# 1_mcuv4.net
KiCad netlist of a schematic drawn in Altium Designer
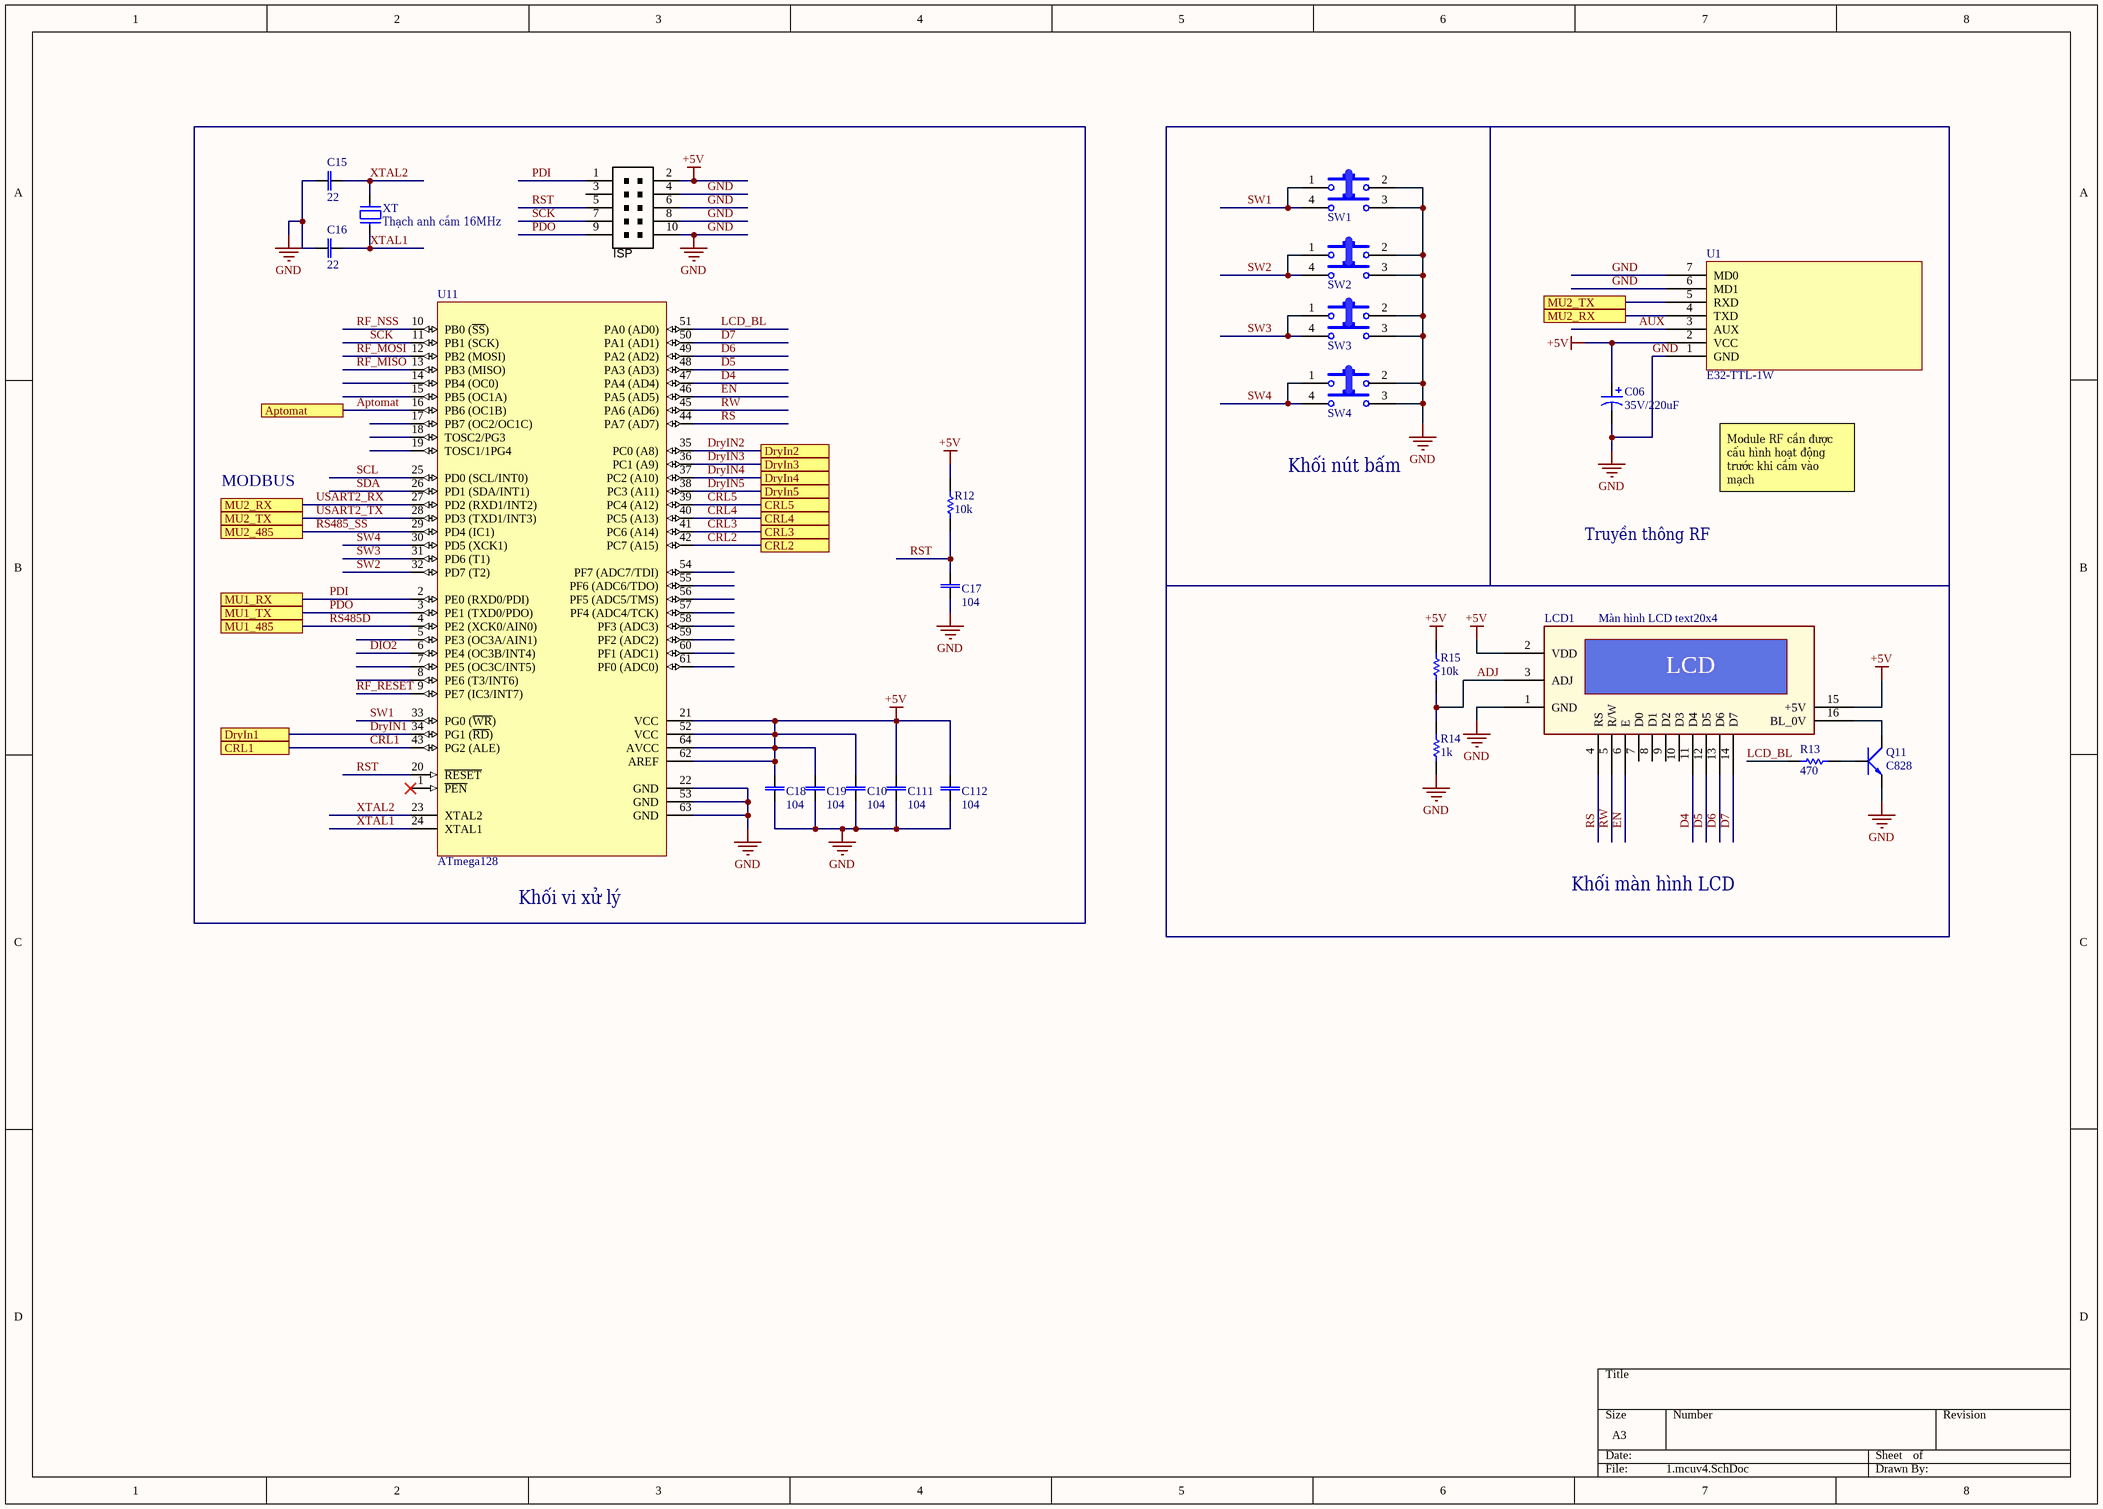
[diagram p0: 1.mcuv4.SchDoc]

(export (version "E")
  (design (tool "Eeschema 10.0.6"))
  (components
    (comp (ref "C06")
      (value "35V/220uF")
      (footprint "CAPE3.5-5.0MM_Rad_10x14mm")
      (fields (field (name "Comment") "Tụ nhôm cắm35V/220uF"))
      (libsource (lib "Tuan") (part "Cap"))
    )
    (comp (ref "C10")
      (value "104")
      (footprint "swatpcblib:CAP 0805")
      (description "Capacitor non polarized")
      (fields (field (name "Comment") "Tụ điện dán 0805104"))
      (libsource (lib "swatpcblib") (part "CAP NP"))
    )
    (comp (ref "C15")
      (value "22")
      (footprint "swatpcblib:CAP 0805")
      (description "Capacitor non polarized")
      (fields (field (name "Comment") "Tụ điện dán 080522"))
      (libsource (lib "swatpcblib") (part "CAP NP"))
    )
    (comp (ref "C16")
      (value "22")
      (footprint "swatpcblib:CAP 0805")
      (description "Capacitor non polarized")
      (fields (field (name "Comment") "Tụ điện dán 080522"))
      (libsource (lib "swatpcblib") (part "CAP NP"))
    )
    (comp (ref "C17")
      (value "104")
      (footprint "swatpcblib:CAP 0805")
      (description "Capacitor non polarized")
      (fields (field (name "Comment") "Tụ điện dán 0805104"))
      (libsource (lib "swatpcblib") (part "CAP NP"))
    )
    (comp (ref "C18")
      (value "104")
      (footprint "swatpcblib:CAP 0805")
      (description "Capacitor non polarized")
      (fields (field (name "Comment") "Tụ điện dán 0805104"))
      (libsource (lib "swatpcblib") (part "CAP NP"))
    )
    (comp (ref "C19")
      (value "104")
      (footprint "swatpcblib:CAP 0805")
      (description "Capacitor non polarized")
      (fields (field (name "Comment") "Tụ điện dán 0805104"))
      (libsource (lib "swatpcblib") (part "CAP NP"))
    )
    (comp (ref "C111")
      (value "104")
      (footprint "swatpcblib:CAP 0805")
      (description "Capacitor non polarized")
      (fields (field (name "Comment") "Tụ điện dán 0805104"))
      (libsource (lib "swatpcblib") (part "CAP NP"))
    )
    (comp (ref "C112")
      (value "104")
      (footprint "swatpcblib:CAP 0805")
      (description "Capacitor non polarized")
      (fields (field (name "Comment") "Tụ điện dán 0805104"))
      (libsource (lib "swatpcblib") (part "CAP NP"))
    )
    (comp (ref "ISP")
      (value "Giắc đôi 5x2 chân 2.54mm")
      (footprint "10P_PCB_HEADER_BRD_MNT")
      (description "Header THD 10 POS Double-row 2.54mm pitch")
      (libsource (lib "PBL - Connectors") (part "CONN_HEADER_2x5P_0.100in_Male"))
    )
    (comp (ref "LCD1")
      (value "Màn hình LCD text20x4")
      (footprint "LCD 20x4")
      (description "Text LCD")
      (libsource (lib "Tuan") (part "LCD 16x2"))
    )
    (comp (ref "Q11")
      (value "C828")
      (footprint "SOT23 TOP")
      (description "Transistor C828 C1815....")
      (libsource (lib "Tuan") (part "NPN"))
    )
    (comp (ref "R12")
      (value "10k")
      (footprint "swatpcblib:RES 0805")
      (description "Resistor")
      (fields (field (name "Comment") "Điện trở dán 080510k"))
      (libsource (lib "swatpcblib") (part "Res"))
    )
    (comp (ref "R13")
      (value "470")
      (footprint "PBL - SMD Packages:RESC1608N_F")
      (description "Resistor")
      (fields (field (name "Comment") "Điện trở dán 0805470"))
      (libsource (lib "swatpcblib") (part "Res"))
    )
    (comp (ref "R14")
      (value "1k")
      (footprint "swatpcblib:RES 0805")
      (description "Resistor")
      (fields (field (name "Comment") "Điện trở dán 08051k"))
      (libsource (lib "swatpcblib") (part "Res"))
    )
    (comp (ref "R15")
      (value "10k")
      (footprint "swatpcblib:RES 0805")
      (description "Resistor")
      (fields (field (name "Comment") "Điện trở dán 080510k"))
      (libsource (lib "swatpcblib") (part "Res"))
    )
    (comp (ref "SW1")
      (value "Nút bấm 4 chân cắm12x12x17mm")
      (footprint "hayqua:SW 12x12x4")
      (libsource (lib "Tuan") (part "SW-4P-Small"))
    )
    (comp (ref "SW2")
      (value "Nút bấm 4 chân cắm12x12x17mm")
      (footprint "hayqua:SW 12x12x4")
      (libsource (lib "Tuan") (part "SW-4P-Small"))
    )
    (comp (ref "SW3")
      (value "Nút bấm 4 chân cắm12x12x17mm")
      (footprint "hayqua:SW 12x12x4")
      (libsource (lib "Tuan") (part "SW-4P-Small"))
    )
    (comp (ref "SW4")
      (value "Nút bấm 4 chân cắm12x12x17mm")
      (footprint "hayqua:SW 12x12x4")
      (libsource (lib "Tuan") (part "SW-4P-Small"))
    )
    (comp (ref "U1")
      (value "E32-TTL-1W")
      (footprint "RF_AS32")
      (description "AS32-TTL-1W")
      (fields (field (name "Comment") "Module thu phát không dây RFE32-TTL-1W"))
      (libsource (lib "DnsSchLib") (part "AS32-TTL-1W"))
    )
    (comp (ref "U11")
      (value "ATmega128")
      (footprint "64A_N")
      (description "8-Bit AVR Microcontroller with 128K Bytes of In-System Programmable Flash Memory")
      (fields (field (name "PUBLISHER") "Altium Limited"))
      (libsource (lib "Atmel Microcontroller 8-Bit AVR") (part "ATmega128-16AC"))
    )
    (comp (ref "XT")
      (value "Thạch anh cắm 16MHz")
      (footprint "XT2")
      (libsource (lib "Tuan") (part "Crystal"))
    )
  )
  (nets
    (net (code "1") (name "+5V") (class "Default")
      (node (ref "C06") (pin "1") (pinfunction "1_1") (pintype "passive"))
      (node (ref "C10") (pin "2") (pinfunction "2_2") (pintype "passive"))
      (node (ref "C111") (pin "2") (pinfunction "2_2") (pintype "passive"))
      (node (ref "C112") (pin "2") (pinfunction "2_2") (pintype "passive"))
      (node (ref "C18") (pin "2") (pinfunction "2_2") (pintype "passive"))
      (node (ref "C19") (pin "2") (pinfunction "2_2") (pintype "passive"))
      (node (ref "ISP") (pin "2") (pinfunction "2_2") (pintype "passive"))
      (node (ref "LCD1") (pin "15") (pinfunction "+5V_15") (pintype "passive"))
      (node (ref "LCD1") (pin "2") (pinfunction "VDD_2") (pintype "passive"))
      (node (ref "R12") (pin "2") (pinfunction "2_2") (pintype "passive"))
      (node (ref "R15") (pin "2") (pinfunction "2_2") (pintype "passive"))
      (node (ref "U1") (pin "2") (pinfunction "VCC_2") (pintype "passive"))
      (node (ref "U11") (pin "21") (pinfunction "VCC_21") (pintype "power_in"))
      (node (ref "U11") (pin "52") (pinfunction "VCC_52") (pintype "power_in"))
      (node (ref "U11") (pin "62") (pinfunction "AREF_62") (pintype "passive"))
      (node (ref "U11") (pin "64") (pinfunction "AVCC_64") (pintype "power_in"))
    )
    (net (code "2") (name "/ADJ") (class "Default")
      (node (ref "LCD1") (pin "3") (pinfunction "ADJ_3") (pintype "passive"))
      (node (ref "R14") (pin "2") (pinfunction "2_2") (pintype "passive"))
      (node (ref "R15") (pin "1") (pinfunction "1_1") (pintype "passive"))
    )
    (net (code "3") (name "/AUX") (class "Default")
      (node (ref "U1") (pin "3") (pinfunction "AUX_3") (pintype "passive"))
    )
    (net (code "4") (name "/Aptomat") (class "Default")
      (node (ref "U11") (pin "16") (pinfunction "PB6_(OC1B)_16") (pintype "bidirectional"))
    )
    (net (code "5") (name "/CRL1") (class "Default")
      (node (ref "U11") (pin "43") (pinfunction "PG2_(ALE)_43") (pintype "bidirectional"))
    )
    (net (code "6") (name "/CRL2") (class "Default")
      (node (ref "U11") (pin "42") (pinfunction "PC7_(A15)_42") (pintype "bidirectional"))
    )
    (net (code "7") (name "/CRL3") (class "Default")
      (node (ref "U11") (pin "41") (pinfunction "PC6_(A14)_41") (pintype "bidirectional"))
    )
    (net (code "8") (name "/CRL4") (class "Default")
      (node (ref "U11") (pin "40") (pinfunction "PC5_(A13)_40") (pintype "bidirectional"))
    )
    (net (code "9") (name "/CRL5") (class "Default")
      (node (ref "U11") (pin "39") (pinfunction "PC4_(A12)_39") (pintype "bidirectional"))
    )
    (net (code "10") (name "/D4") (class "Default")
      (node (ref "LCD1") (pin "11") (pinfunction "D4_11") (pintype "passive"))
      (node (ref "U11") (pin "47") (pinfunction "PA4_(AD4)_47") (pintype "bidirectional"))
    )
    (net (code "11") (name "/D5") (class "Default")
      (node (ref "LCD1") (pin "12") (pinfunction "D5_12") (pintype "passive"))
      (node (ref "U11") (pin "48") (pinfunction "PA3_(AD3)_48") (pintype "bidirectional"))
    )
    (net (code "12") (name "/D6") (class "Default")
      (node (ref "LCD1") (pin "13") (pinfunction "D6_13") (pintype "passive"))
      (node (ref "U11") (pin "49") (pinfunction "PA2_(AD2)_49") (pintype "bidirectional"))
    )
    (net (code "13") (name "/D7") (class "Default")
      (node (ref "LCD1") (pin "14") (pinfunction "D7_14") (pintype "passive"))
      (node (ref "U11") (pin "50") (pinfunction "PA1_(AD1)_50") (pintype "bidirectional"))
    )
    (net (code "14") (name "/DIO2") (class "Default")
      (node (ref "U11") (pin "6") (pinfunction "PE4_(OC3B/INT4)_6") (pintype "bidirectional"))
    )
    (net (code "15") (name "/DryIN1") (class "Default")
      (node (ref "U11") (pin "34") (pinfunction "PG1_(~{RD})_34") (pintype "bidirectional"))
    )
    (net (code "16") (name "/DryIN2") (class "Default")
      (node (ref "U11") (pin "35") (pinfunction "PC0_(A8)_35") (pintype "bidirectional"))
    )
    (net (code "17") (name "/DryIN3") (class "Default")
      (node (ref "U11") (pin "36") (pinfunction "PC1_(A9)_36") (pintype "bidirectional"))
    )
    (net (code "18") (name "/DryIN4") (class "Default")
      (node (ref "U11") (pin "37") (pinfunction "PC2_(A10)_37") (pintype "bidirectional"))
    )
    (net (code "19") (name "/DryIN5") (class "Default")
      (node (ref "U11") (pin "38") (pinfunction "PC3_(A11)_38") (pintype "bidirectional"))
    )
    (net (code "20") (name "/EN") (class "Default")
      (node (ref "LCD1") (pin "6") (pinfunction "E_6") (pintype "passive"))
      (node (ref "U11") (pin "46") (pinfunction "PA5_(AD5)_46") (pintype "bidirectional"))
    )
    (net (code "21") (name "/LCD_BL") (class "Default")
      (node (ref "R13") (pin "2") (pinfunction "2_2") (pintype "passive"))
      (node (ref "U11") (pin "51") (pinfunction "PA0_(AD0)_51") (pintype "bidirectional"))
    )
    (net (code "22") (name "/PDI") (class "Default")
      (node (ref "ISP") (pin "1") (pinfunction "1_1") (pintype "passive"))
      (node (ref "U11") (pin "2") (pinfunction "PE0_(RXD0/PDI)_2") (pintype "bidirectional"))
    )
    (net (code "23") (name "/PDO") (class "Default")
      (node (ref "ISP") (pin "9") (pinfunction "9_9") (pintype "passive"))
      (node (ref "U11") (pin "3") (pinfunction "PE1_(TXD0/PDO)_3") (pintype "bidirectional"))
    )
    (net (code "24") (name "/RF_MISO") (class "Default")
      (node (ref "U11") (pin "13") (pinfunction "PB3_(MISO)_13") (pintype "bidirectional"))
    )
    (net (code "25") (name "/RF_MOSI") (class "Default")
      (node (ref "U11") (pin "12") (pinfunction "PB2_(MOSI)_12") (pintype "bidirectional"))
    )
    (net (code "26") (name "/RF_NSS") (class "Default")
      (node (ref "U11") (pin "10") (pinfunction "PB0_(~{SS})_10") (pintype "bidirectional"))
    )
    (net (code "27") (name "/RF_RESET") (class "Default")
      (node (ref "U11") (pin "9") (pinfunction "PE7_(IC3/INT7)_9") (pintype "bidirectional"))
    )
    (net (code "28") (name "/RS") (class "Default")
      (node (ref "LCD1") (pin "4") (pinfunction "RS_4") (pintype "passive"))
      (node (ref "U11") (pin "44") (pinfunction "PA7_(AD7)_44") (pintype "bidirectional"))
    )
    (net (code "29") (name "/RS485D") (class "Default")
      (node (ref "U11") (pin "4") (pinfunction "PE2_(XCK0/AIN0)_4") (pintype "bidirectional"))
    )
    (net (code "30") (name "/RS485_SS") (class "Default")
      (node (ref "U11") (pin "29") (pinfunction "PD4_(IC1)_29") (pintype "bidirectional"))
    )
    (net (code "31") (name "/RST") (class "Default")
      (node (ref "C17") (pin "2") (pinfunction "2_2") (pintype "passive"))
      (node (ref "ISP") (pin "5") (pinfunction "5_5") (pintype "passive"))
      (node (ref "R12") (pin "1") (pinfunction "1_1") (pintype "passive"))
      (node (ref "U11") (pin "20") (pinfunction "~{RESET}_20") (pintype "input"))
    )
    (net (code "32") (name "/RW") (class "Default")
      (node (ref "LCD1") (pin "5") (pinfunction "R/W_5") (pintype "passive"))
      (node (ref "U11") (pin "45") (pinfunction "PA6_(AD6)_45") (pintype "bidirectional"))
    )
    (net (code "33") (name "/SCK") (class "Default")
      (node (ref "ISP") (pin "7") (pinfunction "7_7") (pintype "passive"))
      (node (ref "U11") (pin "11") (pinfunction "PB1_(SCK)_11") (pintype "bidirectional"))
    )
    (net (code "34") (name "/SCL") (class "Default")
      (node (ref "U11") (pin "25") (pinfunction "PD0_(SCL/INT0)_25") (pintype "bidirectional"))
    )
    (net (code "35") (name "/SDA") (class "Default")
      (node (ref "U11") (pin "26") (pinfunction "PD1_(SDA/INT1)_26") (pintype "bidirectional"))
    )
    (net (code "36") (name "/SW1") (class "Default")
      (node (ref "SW1") (pin "1") (pinfunction "1_1") (pintype "passive"))
      (node (ref "SW1") (pin "4") (pinfunction "4_4") (pintype "passive"))
      (node (ref "U11") (pin "33") (pinfunction "PG0_(~{WR})_33") (pintype "bidirectional"))
    )
    (net (code "37") (name "/SW2") (class "Default")
      (node (ref "SW2") (pin "1") (pinfunction "1_1") (pintype "passive"))
      (node (ref "SW2") (pin "4") (pinfunction "4_4") (pintype "passive"))
      (node (ref "U11") (pin "32") (pinfunction "PD7_(T2)_32") (pintype "bidirectional"))
    )
    (net (code "38") (name "/SW3") (class "Default")
      (node (ref "SW3") (pin "1") (pinfunction "1_1") (pintype "passive"))
      (node (ref "SW3") (pin "4") (pinfunction "4_4") (pintype "passive"))
      (node (ref "U11") (pin "31") (pinfunction "PD6_(T1)_31") (pintype "bidirectional"))
    )
    (net (code "39") (name "/SW4") (class "Default")
      (node (ref "SW4") (pin "1") (pinfunction "1_1") (pintype "passive"))
      (node (ref "SW4") (pin "4") (pinfunction "4_4") (pintype "passive"))
      (node (ref "U11") (pin "30") (pinfunction "PD5_(XCK1)_30") (pintype "bidirectional"))
    )
    (net (code "40") (name "/USART2_RX") (class "Default")
      (node (ref "U1") (pin "4") (pinfunction "TXD_4") (pintype "passive"))
      (node (ref "U11") (pin "27") (pinfunction "PD2_(RXD1/INT2)_27") (pintype "bidirectional"))
    )
    (net (code "41") (name "/USART2_TX") (class "Default")
      (node (ref "U1") (pin "5") (pinfunction "RXD_5") (pintype "passive"))
      (node (ref "U11") (pin "28") (pinfunction "PD3_(TXD1/INT3)_28") (pintype "bidirectional"))
    )
    (net (code "42") (name "/XTAL1") (class "Default")
      (node (ref "C16") (pin "1") (pinfunction "1_1") (pintype "passive"))
      (node (ref "U11") (pin "24") (pinfunction "XTAL1_24") (pintype "passive"))
      (node (ref "XT") (pin "1") (pinfunction "1_1") (pintype "passive"))
    )
    (net (code "43") (name "/XTAL2") (class "Default")
      (node (ref "C15") (pin "1") (pinfunction "1_1") (pintype "passive"))
      (node (ref "U11") (pin "23") (pinfunction "XTAL2_23") (pintype "passive"))
      (node (ref "XT") (pin "2") (pinfunction "2_2") (pintype "passive"))
    )
    (net (code "44") (name "GND") (class "Default")
      (node (ref "C06") (pin "2") (pinfunction "2_2") (pintype "passive"))
      (node (ref "C10") (pin "1") (pinfunction "1_1") (pintype "passive"))
      (node (ref "C111") (pin "1") (pinfunction "1_1") (pintype "passive"))
      (node (ref "C112") (pin "1") (pinfunction "1_1") (pintype "passive"))
      (node (ref "C15") (pin "2") (pinfunction "2_2") (pintype "passive"))
      (node (ref "C16") (pin "2") (pinfunction "2_2") (pintype "passive"))
      (node (ref "C17") (pin "1") (pinfunction "1_1") (pintype "passive"))
      (node (ref "C18") (pin "1") (pinfunction "1_1") (pintype "passive"))
      (node (ref "C19") (pin "1") (pinfunction "1_1") (pintype "passive"))
      (node (ref "ISP") (pin "10") (pinfunction "10_10") (pintype "passive"))
      (node (ref "ISP") (pin "4") (pinfunction "4_4") (pintype "passive"))
      (node (ref "ISP") (pin "6") (pinfunction "6_6") (pintype "passive"))
      (node (ref "ISP") (pin "8") (pinfunction "8_8") (pintype "passive"))
      (node (ref "LCD1") (pin "1") (pinfunction "GND_1") (pintype "passive"))
      (node (ref "Q11") (pin "3") (pinfunction "E_3") (pintype "passive"))
      (node (ref "R14") (pin "1") (pinfunction "1_1") (pintype "passive"))
      (node (ref "SW1") (pin "2") (pinfunction "2_2") (pintype "passive"))
      (node (ref "SW1") (pin "3") (pinfunction "3_3") (pintype "passive"))
      (node (ref "SW2") (pin "2") (pinfunction "2_2") (pintype "passive"))
      (node (ref "SW2") (pin "3") (pinfunction "3_3") (pintype "passive"))
      (node (ref "SW3") (pin "2") (pinfunction "2_2") (pintype "passive"))
      (node (ref "SW3") (pin "3") (pinfunction "3_3") (pintype "passive"))
      (node (ref "SW4") (pin "2") (pinfunction "2_2") (pintype "passive"))
      (node (ref "SW4") (pin "3") (pinfunction "3_3") (pintype "passive"))
      (node (ref "U1") (pin "1") (pinfunction "GND_1") (pintype "passive"))
      (node (ref "U1") (pin "6") (pinfunction "MD1_6") (pintype "passive"))
      (node (ref "U1") (pin "7") (pinfunction "MD0_7") (pintype "passive"))
      (node (ref "U11") (pin "22") (pinfunction "GND_22") (pintype "power_in"))
      (node (ref "U11") (pin "53") (pinfunction "GND_53") (pintype "power_in"))
      (node (ref "U11") (pin "63") (pinfunction "GND_63") (pintype "power_in"))
    )
    (net (code "45") (name "Net-(LCD1-BL_0V)") (class "Default")
      (node (ref "LCD1") (pin "16") (pinfunction "BL_0V_16") (pintype "passive"))
      (node (ref "Q11") (pin "2") (pinfunction "C_2") (pintype "passive"))
    )
    (net (code "46") (name "Net-(Q11-B)") (class "Default")
      (node (ref "Q11") (pin "1") (pinfunction "B_1") (pintype "passive"))
      (node (ref "R13") (pin "1") (pinfunction "1_1") (pintype "passive"))
    )
    (net (code "47") (name "unconnected-(ISP-Pad3)") (class "Default")
      (node (ref "ISP") (pin "3") (pinfunction "3_3") (pintype "passive"))
    )
    (net (code "48") (name "unconnected-(LCD1-D0-Pad7)") (class "Default")
      (node (ref "LCD1") (pin "7") (pinfunction "D0_7") (pintype "passive"))
    )
    (net (code "49") (name "unconnected-(LCD1-D1-Pad8)") (class "Default")
      (node (ref "LCD1") (pin "8") (pinfunction "D1_8") (pintype "passive"))
    )
    (net (code "50") (name "unconnected-(LCD1-D2-Pad9)") (class "Default")
      (node (ref "LCD1") (pin "9") (pinfunction "D2_9") (pintype "passive"))
    )
    (net (code "51") (name "unconnected-(LCD1-D3-Pad10)") (class "Default")
      (node (ref "LCD1") (pin "10") (pinfunction "D3_10") (pintype "passive"))
    )
    (net (code "52") (name "unconnected-(U11-PB4_(OC0)-Pad14)") (class "Default")
      (node (ref "U11") (pin "14") (pinfunction "PB4_(OC0)_14") (pintype "bidirectional"))
    )
    (net (code "53") (name "unconnected-(U11-PB5_(OC1A)-Pad15)") (class "Default")
      (node (ref "U11") (pin "15") (pinfunction "PB5_(OC1A)_15") (pintype "bidirectional"))
    )
    (net (code "54") (name "unconnected-(U11-PB7_(OC2{slash}OC1C)-Pad17)") (class "Default")
      (node (ref "U11") (pin "17") (pinfunction "PB7_(OC2/OC1C)_17") (pintype "bidirectional"))
    )
    (net (code "55") (name "unconnected-(U11-PE3_(OC3A{slash}AIN1)-Pad5)") (class "Default")
      (node (ref "U11") (pin "5") (pinfunction "PE3_(OC3A/AIN1)_5") (pintype "bidirectional"))
    )
    (net (code "56") (name "unconnected-(U11-PE5_(OC3C{slash}INT5)-Pad7)") (class "Default")
      (node (ref "U11") (pin "7") (pinfunction "PE5_(OC3C/INT5)_7") (pintype "bidirectional"))
    )
    (net (code "57") (name "unconnected-(U11-PE6_(T3{slash}INT6)-Pad8)") (class "Default")
      (node (ref "U11") (pin "8") (pinfunction "PE6_(T3/INT6)_8") (pintype "bidirectional"))
    )
    (net (code "58") (name "unconnected-(U11-PF0_(ADC0)-Pad61)") (class "Default")
      (node (ref "U11") (pin "61") (pinfunction "PF0_(ADC0)_61") (pintype "bidirectional"))
    )
    (net (code "59") (name "unconnected-(U11-PF1_(ADC1)-Pad60)") (class "Default")
      (node (ref "U11") (pin "60") (pinfunction "PF1_(ADC1)_60") (pintype "bidirectional"))
    )
    (net (code "60") (name "unconnected-(U11-PF2_(ADC2)-Pad59)") (class "Default")
      (node (ref "U11") (pin "59") (pinfunction "PF2_(ADC2)_59") (pintype "bidirectional"))
    )
    (net (code "61") (name "unconnected-(U11-PF3_(ADC3)-Pad58)") (class "Default")
      (node (ref "U11") (pin "58") (pinfunction "PF3_(ADC3)_58") (pintype "bidirectional"))
    )
    (net (code "62") (name "unconnected-(U11-PF4_(ADC4{slash}TCK)-Pad57)") (class "Default")
      (node (ref "U11") (pin "57") (pinfunction "PF4_(ADC4/TCK)_57") (pintype "bidirectional"))
    )
    (net (code "63") (name "unconnected-(U11-PF5_(ADC5{slash}TMS)-Pad56)") (class "Default")
      (node (ref "U11") (pin "56") (pinfunction "PF5_(ADC5/TMS)_56") (pintype "bidirectional"))
    )
    (net (code "64") (name "unconnected-(U11-PF6_(ADC6{slash}TDO)-Pad55)") (class "Default")
      (node (ref "U11") (pin "55") (pinfunction "PF6_(ADC6/TDO)_55") (pintype "bidirectional"))
    )
    (net (code "65") (name "unconnected-(U11-PF7_(ADC7{slash}TDI)-Pad54)") (class "Default")
      (node (ref "U11") (pin "54") (pinfunction "PF7_(ADC7/TDI)_54") (pintype "bidirectional"))
    )
    (net (code "66") (name "unconnected-(U11-TOSC1{slash}1PG4-Pad19)") (class "Default")
      (node (ref "U11") (pin "19") (pinfunction "TOSC1/1PG4_19") (pintype "bidirectional"))
    )
    (net (code "67") (name "unconnected-(U11-TOSC2{slash}PG3-Pad18)") (class "Default")
      (node (ref "U11") (pin "18") (pinfunction "TOSC2/PG3_18") (pintype "bidirectional"))
    )
    (net (code "68") (name "unconnected-(U11-~{PEN}-Pad1)") (class "Default")
      (node (ref "U11") (pin "1") (pinfunction "~{PEN}_1") (pintype "input+no_connect"))
    )
  )
)
